# Meshtastic-DIY_v2.net
KiCad netlist of a schematic drawn in EAGLE
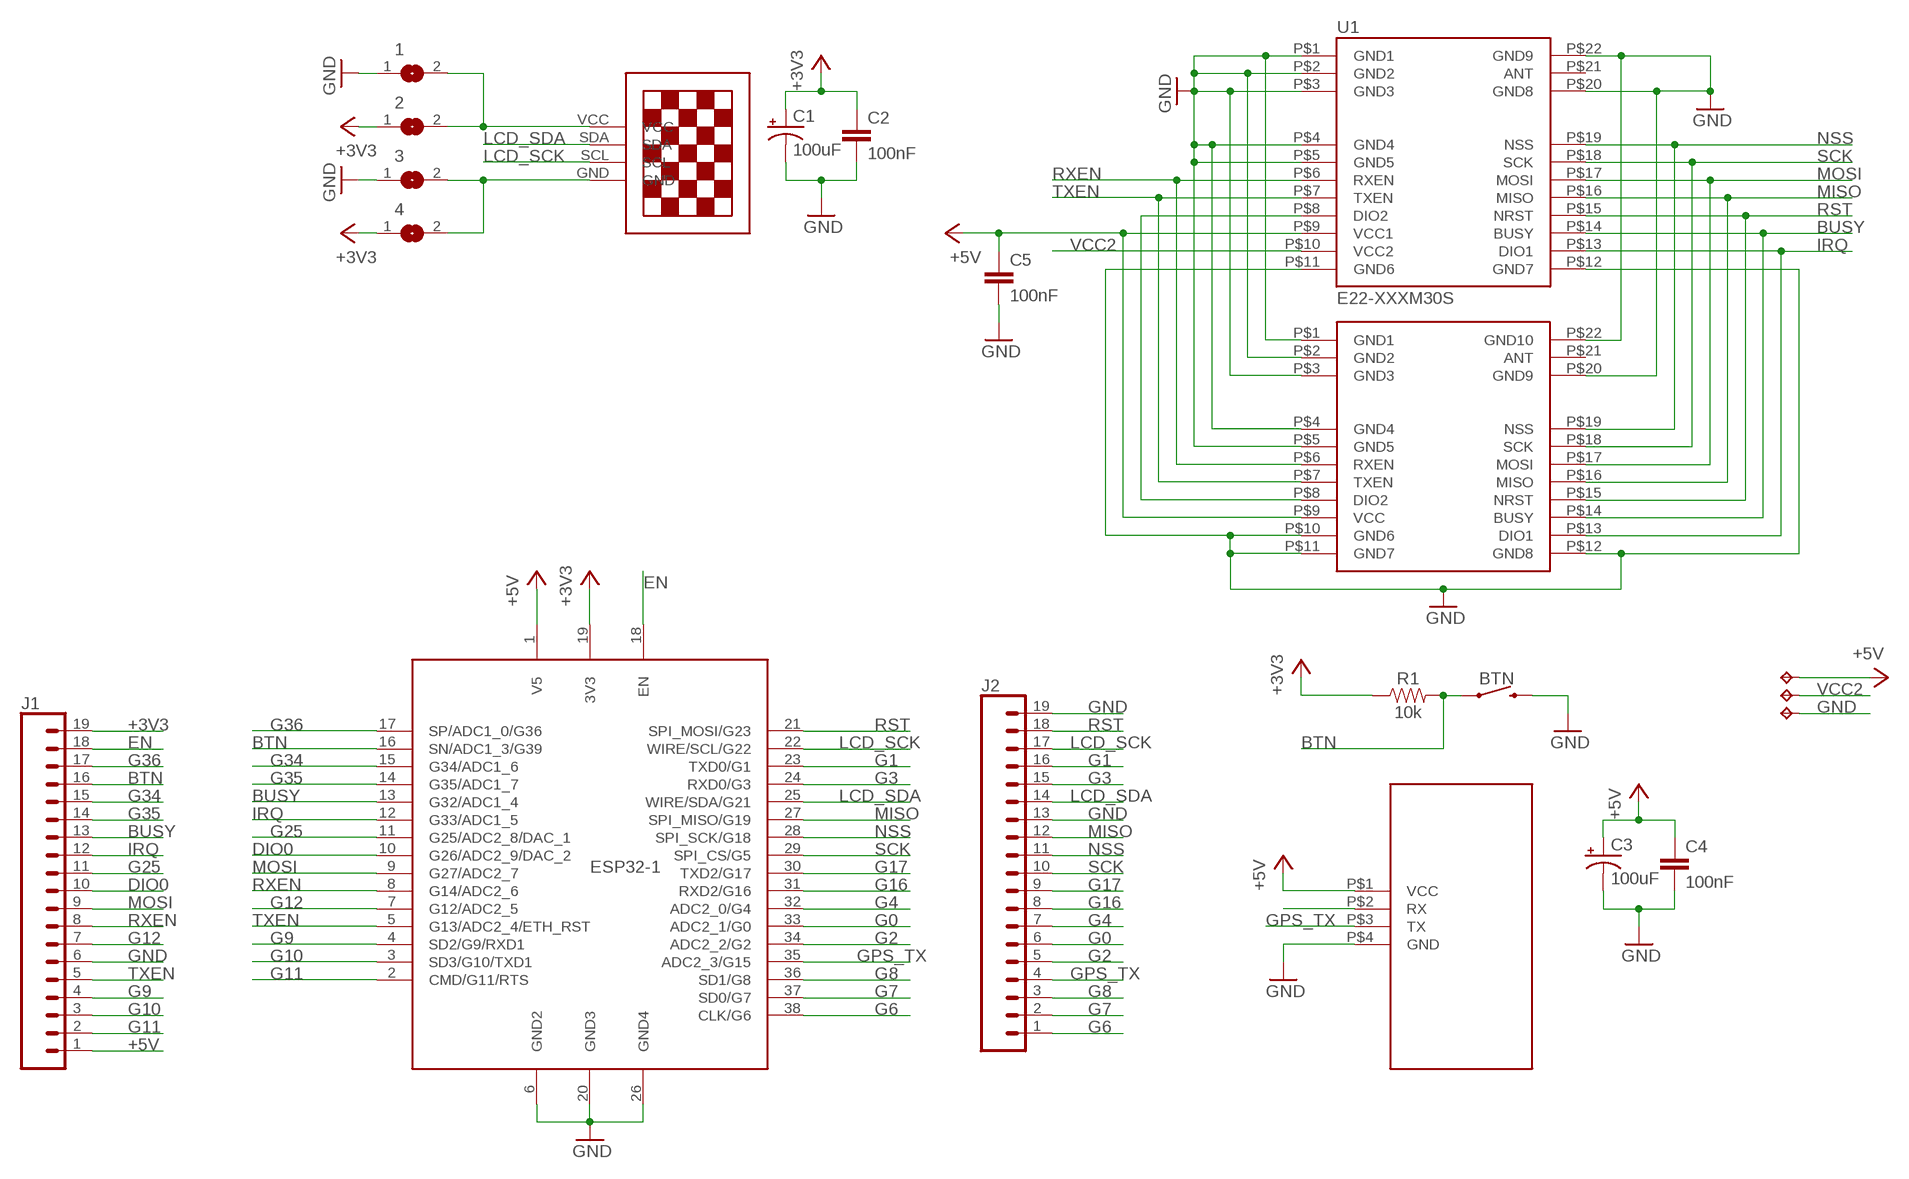
[diagram p0: schematic, sheet 1]

(export (version "E")
  (design (tool "Eeschema 10.0.6"))
  (components
    (comp (ref "1") (value "SJ") (footprint "eagle-import:SJ") (libsource (lib "eagle-import") (part "SJ")))
    (comp (ref "2") (value "SJ") (footprint "eagle-import:SJ") (libsource (lib "eagle-import") (part "SJ")))
    (comp (ref "3") (value "SJ") (footprint "eagle-import:SJ") (libsource (lib "eagle-import") (part "SJ")))
    (comp (ref "4") (value "SJ") (footprint "eagle-import:SJ") (libsource (lib "eagle-import") (part "SJ")))
    (comp (ref "BTN")
      (value "MOMENTARY-SWITCH-SPST-PTH-6.0MM")
      (footprint "eagle-import:TACTILE_SWITCH_PTH_6.0MM")
      (libsource (lib "eagle-import") (part "MOMENTARY-SWITCH-SPST-PTH-6.0MM"))
    )
    (comp (ref "C1")
      (value "100uF")
      (footprint "eagle-import:EIA7343")
      (libsource (lib "eagle-import") (part "100UF-POLAR-EIA7343-10V-10%(TANT)"))
    )
    (comp (ref "C2")
      (value "100nF")
      (footprint "eagle-import:0805")
      (libsource (lib "eagle-import") (part "0.33UF/330NF-0805-50V-10%"))
    )
    (comp (ref "C3")
      (value "100uF")
      (footprint "eagle-import:EIA7343")
      (libsource (lib "eagle-import") (part "100UF-POLAR-EIA7343-10V-10%(TANT)"))
    )
    (comp (ref "C4")
      (value "100nF")
      (footprint "eagle-import:0805")
      (libsource (lib "eagle-import") (part "0.33UF/330NF-0805-50V-10%"))
    )
    (comp (ref "C5")
      (value "100nF")
      (footprint "eagle-import:0805")
      (libsource (lib "eagle-import") (part "0.33UF/330NF-0805-50V-10%"))
    )
    (comp (ref "ESP32-1")
      (value "NODEMCU_ESP32_WROOM_32")
      (footprint "eagle-import:NODEMCU_ESP32_WROOM_32--38PINS")
      (libsource (lib "eagle-import") (part "NODEMCU_ESP32_WROOM_32"))
    )
    (comp (ref "J1")
      (value "CONN_191X19_NO_SILK")
      (footprint "eagle-import:1X19_NO_SILK")
      (libsource (lib "eagle-import") (part "CONN_191X19_NO_SILK"))
    )
    (comp (ref "J2")
      (value "CONN_191X19_NO_SILK")
      (footprint "eagle-import:1X19_NO_SILK")
      (libsource (lib "eagle-import") (part "CONN_191X19_NO_SILK"))
    )
    (comp (ref "R1")
      (value "10k")
      (footprint "eagle-import:1210")
      (libsource (lib "eagle-import") (part "0.1OHM-1210-1/2W-1%"))
    )
    (comp (ref "TP1")
      (value "TPTP14SQ")
      (footprint "eagle-import:TP14SQ")
      (libsource (lib "eagle-import") (part "TPTP14SQ"))
    )
    (comp (ref "TP2")
      (value "TPTP14SQ")
      (footprint "eagle-import:TP14SQ")
      (libsource (lib "eagle-import") (part "TPTP14SQ"))
    )
    (comp (ref "TP3")
      (value "TPTP14SQ")
      (footprint "eagle-import:TP14SQ")
      (libsource (lib "eagle-import") (part "TPTP14SQ"))
    )
    (comp (ref "U$1")
      (value "13\"OLED13\"OLED")
      (footprint "eagle-import:1.3_OLED")
      (libsource (lib "eagle-import") (part "13{dblquote}OLED13{dblquote}OLED"))
    )
    (comp (ref "U$2")
      (value "E22-XXXM22S")
      (footprint "eagle-import:E22-XXXM22S")
      (libsource (lib "eagle-import") (part "E22-XXXM22S"))
    )
    (comp (ref "U$3")
      (value "GPS-NEO")
      (footprint "eagle-import:GPS-NEO")
      (libsource (lib "eagle-import") (part "GPS-NEO"))
    )
    (comp (ref "U1")
      (value "E22-XXXM30S")
      (footprint "eagle-import:E22-XXXM30S")
      (libsource (lib "eagle-import") (part "E22-XXXM30S"))
    )
  )
  (nets
    (net (code "1") (name "+3V3") (class "Default")
      (node (ref "2") (pin "1") (pinfunction "1_1") (pintype "passive"))
      (node (ref "4") (pin "1") (pinfunction "1_1") (pintype "passive"))
      (node (ref "C1") (pin "A") (pinfunction "+_A") (pintype "passive"))
      (node (ref "C2") (pin "1") (pinfunction "1_1") (pintype "passive"))
      (node (ref "ESP32-1") (pin "19") (pinfunction "3V3_19") (pintype "power_in"))
      (node (ref "J1") (pin "19") (pinfunction "19_19") (pintype "passive"))
      (node (ref "R1") (pin "1") (pinfunction "1_1") (pintype "passive"))
    )
    (net (code "2") (name "+5V") (class "Default")
      (node (ref "C3") (pin "A") (pinfunction "+_A") (pintype "passive"))
      (node (ref "C4") (pin "1") (pinfunction "1_1") (pintype "passive"))
      (node (ref "C5") (pin "1") (pinfunction "1_1") (pintype "passive"))
      (node (ref "ESP32-1") (pin "1") (pinfunction "V5_1") (pintype "power_in"))
      (node (ref "J1") (pin "1") (pinfunction "1_1") (pintype "passive"))
      (node (ref "TP1") (pin "TP") (pinfunction "TP_TP") (pintype "input"))
      (node (ref "U$2") (pin "P$9") (pinfunction "VCC_P$9") (pintype "bidirectional"))
      (node (ref "U$3") (pin "P$1") (pinfunction "VCC_P$1") (pintype "bidirectional"))
      (node (ref "U1") (pin "P$9") (pinfunction "VCC1_P$9") (pintype "bidirectional"))
    )
    (net (code "3") (name "/BTN") (class "Default")
      (node (ref "BTN") (pin "1") (pinfunction "1_1") (pintype "passive"))
      (node (ref "ESP32-1") (pin "16") (pinfunction "SN/ADC1_3/G39_16") (pintype "bidirectional"))
      (node (ref "J1") (pin "16") (pinfunction "16_16") (pintype "passive"))
      (node (ref "R1") (pin "2") (pinfunction "2_2") (pintype "passive"))
    )
    (net (code "4") (name "/BUSY") (class "Default")
      (node (ref "ESP32-1") (pin "13") (pinfunction "G32/ADC1_4_13") (pintype "bidirectional"))
      (node (ref "J1") (pin "13") (pinfunction "13_13") (pintype "passive"))
      (node (ref "U$2") (pin "P$14") (pinfunction "BUSY_P$14") (pintype "bidirectional"))
      (node (ref "U1") (pin "P$14") (pinfunction "BUSY_P$14") (pintype "bidirectional"))
    )
    (net (code "5") (name "/DIO0") (class "Default")
      (node (ref "ESP32-1") (pin "10") (pinfunction "G26/ADC2_9/DAC_2_10") (pintype "bidirectional"))
      (node (ref "J1") (pin "10") (pinfunction "10_10") (pintype "passive"))
    )
    (net (code "6") (name "/EN") (class "Default")
      (node (ref "ESP32-1") (pin "18") (pinfunction "EN_18") (pintype "bidirectional"))
      (node (ref "J1") (pin "18") (pinfunction "18_18") (pintype "passive"))
    )
    (net (code "7") (name "/G0") (class "Default")
      (node (ref "ESP32-1") (pin "33") (pinfunction "ADC2_1/G0_33") (pintype "bidirectional"))
      (node (ref "J2") (pin "6") (pinfunction "6_6") (pintype "passive"))
    )
    (net (code "8") (name "/G1") (class "Default")
      (node (ref "ESP32-1") (pin "23") (pinfunction "TXD0/G1_23") (pintype "bidirectional"))
      (node (ref "J2") (pin "16") (pinfunction "16_16") (pintype "passive"))
    )
    (net (code "9") (name "/G2") (class "Default")
      (node (ref "ESP32-1") (pin "34") (pinfunction "ADC2_2/G2_34") (pintype "bidirectional"))
      (node (ref "J2") (pin "5") (pinfunction "5_5") (pintype "passive"))
    )
    (net (code "10") (name "/G3") (class "Default")
      (node (ref "ESP32-1") (pin "24") (pinfunction "RXD0/G3_24") (pintype "bidirectional"))
      (node (ref "J2") (pin "15") (pinfunction "15_15") (pintype "passive"))
    )
    (net (code "11") (name "/G4") (class "Default")
      (node (ref "ESP32-1") (pin "32") (pinfunction "ADC2_0/G4_32") (pintype "bidirectional"))
      (node (ref "J2") (pin "7") (pinfunction "7_7") (pintype "passive"))
    )
    (net (code "12") (name "/G6") (class "Default")
      (node (ref "ESP32-1") (pin "38") (pinfunction "CLK/G6_38") (pintype "bidirectional"))
      (node (ref "J2") (pin "1") (pinfunction "1_1") (pintype "passive"))
    )
    (net (code "13") (name "/G7") (class "Default")
      (node (ref "ESP32-1") (pin "37") (pinfunction "SD0/G7_37") (pintype "bidirectional"))
      (node (ref "J2") (pin "2") (pinfunction "2_2") (pintype "passive"))
    )
    (net (code "14") (name "/G8") (class "Default")
      (node (ref "ESP32-1") (pin "36") (pinfunction "SD1/G8_36") (pintype "bidirectional"))
      (node (ref "J2") (pin "3") (pinfunction "3_3") (pintype "passive"))
    )
    (net (code "15") (name "/G9") (class "Default")
      (node (ref "ESP32-1") (pin "4") (pinfunction "SD2/G9/RXD1_4") (pintype "bidirectional"))
      (node (ref "J1") (pin "4") (pinfunction "4_4") (pintype "passive"))
    )
    (net (code "16") (name "/G10") (class "Default")
      (node (ref "ESP32-1") (pin "3") (pinfunction "SD3/G10/TXD1_3") (pintype "bidirectional"))
      (node (ref "J1") (pin "3") (pinfunction "3_3") (pintype "passive"))
    )
    (net (code "17") (name "/G11") (class "Default")
      (node (ref "ESP32-1") (pin "2") (pinfunction "CMD/G11/RTS_2") (pintype "power_in"))
      (node (ref "J1") (pin "2") (pinfunction "2_2") (pintype "passive"))
    )
    (net (code "18") (name "/G12") (class "Default")
      (node (ref "ESP32-1") (pin "7") (pinfunction "G12/ADC2_5_7") (pintype "bidirectional"))
      (node (ref "J1") (pin "7") (pinfunction "7_7") (pintype "passive"))
    )
    (net (code "19") (name "/G16") (class "Default")
      (node (ref "ESP32-1") (pin "31") (pinfunction "RXD2/G16_31") (pintype "bidirectional"))
      (node (ref "J2") (pin "8") (pinfunction "8_8") (pintype "passive"))
    )
    (net (code "20") (name "/G17") (class "Default")
      (node (ref "ESP32-1") (pin "30") (pinfunction "TXD2/G17_30") (pintype "bidirectional"))
      (node (ref "J2") (pin "9") (pinfunction "9_9") (pintype "passive"))
    )
    (net (code "21") (name "/G25") (class "Default")
      (node (ref "ESP32-1") (pin "11") (pinfunction "G25/ADC2_8/DAC_1_11") (pintype "bidirectional"))
      (node (ref "J1") (pin "11") (pinfunction "11_11") (pintype "passive"))
    )
    (net (code "22") (name "/G34") (class "Default")
      (node (ref "ESP32-1") (pin "15") (pinfunction "G34/ADC1_6_15") (pintype "bidirectional"))
      (node (ref "J1") (pin "15") (pinfunction "15_15") (pintype "passive"))
    )
    (net (code "23") (name "/G35") (class "Default")
      (node (ref "ESP32-1") (pin "14") (pinfunction "G35/ADC1_7_14") (pintype "bidirectional"))
      (node (ref "J1") (pin "14") (pinfunction "14_14") (pintype "passive"))
    )
    (net (code "24") (name "/G36") (class "Default")
      (node (ref "ESP32-1") (pin "17") (pinfunction "SP/ADC1_0/G36_17") (pintype "bidirectional"))
      (node (ref "J1") (pin "17") (pinfunction "17_17") (pintype "passive"))
    )
    (net (code "25") (name "/GPS_TX") (class "Default")
      (node (ref "ESP32-1") (pin "35") (pinfunction "ADC2_3/G15_35") (pintype "bidirectional"))
      (node (ref "J2") (pin "4") (pinfunction "4_4") (pintype "passive"))
      (node (ref "U$3") (pin "P$3") (pinfunction "TX_P$3") (pintype "bidirectional"))
    )
    (net (code "26") (name "/IRQ") (class "Default")
      (node (ref "ESP32-1") (pin "12") (pinfunction "G33/ADC1_5_12") (pintype "bidirectional"))
      (node (ref "J1") (pin "12") (pinfunction "12_12") (pintype "passive"))
      (node (ref "U$2") (pin "P$13") (pinfunction "DIO1_P$13") (pintype "bidirectional"))
      (node (ref "U1") (pin "P$13") (pinfunction "DIO1_P$13") (pintype "bidirectional"))
    )
    (net (code "27") (name "/LCD_SCK") (class "Default")
      (node (ref "ESP32-1") (pin "22") (pinfunction "WIRE/SCL/G22_22") (pintype "bidirectional"))
      (node (ref "J2") (pin "17") (pinfunction "17_17") (pintype "passive"))
      (node (ref "U$1") (pin "SCL") (pinfunction "SCL_SCL") (pintype "bidirectional"))
    )
    (net (code "28") (name "/LCD_SDA") (class "Default")
      (node (ref "ESP32-1") (pin "25") (pinfunction "WIRE/SDA/G21_25") (pintype "bidirectional"))
      (node (ref "J2") (pin "14") (pinfunction "14_14") (pintype "passive"))
      (node (ref "U$1") (pin "SDA") (pinfunction "SDA_SDA") (pintype "bidirectional"))
    )
    (net (code "29") (name "/MISO") (class "Default")
      (node (ref "ESP32-1") (pin "27") (pinfunction "SPI_MISO/G19_27") (pintype "bidirectional"))
      (node (ref "J2") (pin "12") (pinfunction "12_12") (pintype "passive"))
      (node (ref "U$2") (pin "P$16") (pinfunction "MISO_P$16") (pintype "bidirectional"))
      (node (ref "U1") (pin "P$16") (pinfunction "MISO_P$16") (pintype "bidirectional"))
    )
    (net (code "30") (name "/MOSI") (class "Default")
      (node (ref "ESP32-1") (pin "9") (pinfunction "G27/ADC2_7_9") (pintype "bidirectional"))
      (node (ref "J1") (pin "9") (pinfunction "9_9") (pintype "passive"))
      (node (ref "U$2") (pin "P$17") (pinfunction "MOSI_P$17") (pintype "bidirectional"))
      (node (ref "U1") (pin "P$17") (pinfunction "MOSI_P$17") (pintype "bidirectional"))
    )
    (net (code "31") (name "/NSS") (class "Default")
      (node (ref "ESP32-1") (pin "28") (pinfunction "SPI_SCK/G18_28") (pintype "bidirectional"))
      (node (ref "J2") (pin "11") (pinfunction "11_11") (pintype "passive"))
      (node (ref "U$2") (pin "P$19") (pinfunction "NSS_P$19") (pintype "bidirectional"))
      (node (ref "U1") (pin "P$19") (pinfunction "NSS_P$19") (pintype "bidirectional"))
    )
    (net (code "32") (name "/RST") (class "Default")
      (node (ref "ESP32-1") (pin "21") (pinfunction "SPI_MOSI/G23_21") (pintype "bidirectional"))
      (node (ref "J2") (pin "18") (pinfunction "18_18") (pintype "passive"))
      (node (ref "U$2") (pin "P$15") (pinfunction "NRST_P$15") (pintype "bidirectional"))
      (node (ref "U1") (pin "P$15") (pinfunction "NRST_P$15") (pintype "bidirectional"))
    )
    (net (code "33") (name "/RXEN") (class "Default")
      (node (ref "ESP32-1") (pin "8") (pinfunction "G14/ADC2_6_8") (pintype "bidirectional"))
      (node (ref "J1") (pin "8") (pinfunction "8_8") (pintype "passive"))
      (node (ref "U$2") (pin "P$6") (pinfunction "RXEN_P$6") (pintype "bidirectional"))
      (node (ref "U1") (pin "P$6") (pinfunction "RXEN_P$6") (pintype "bidirectional"))
    )
    (net (code "34") (name "/SCK") (class "Default")
      (node (ref "ESP32-1") (pin "29") (pinfunction "SPI_CS/G5_29") (pintype "bidirectional"))
      (node (ref "J2") (pin "10") (pinfunction "10_10") (pintype "passive"))
      (node (ref "U$2") (pin "P$18") (pinfunction "SCK_P$18") (pintype "bidirectional"))
      (node (ref "U1") (pin "P$18") (pinfunction "SCK_P$18") (pintype "bidirectional"))
    )
    (net (code "35") (name "/TXEN") (class "Default")
      (node (ref "ESP32-1") (pin "5") (pinfunction "G13/ADC2_4/ETH_RST_5") (pintype "bidirectional"))
      (node (ref "J1") (pin "5") (pinfunction "5_5") (pintype "passive"))
      (node (ref "U$2") (pin "P$7") (pinfunction "TXEN_P$7") (pintype "bidirectional"))
      (node (ref "U1") (pin "P$7") (pinfunction "TXEN_P$7") (pintype "bidirectional"))
    )
    (net (code "36") (name "/VCC2") (class "Default")
      (node (ref "TP2") (pin "TP") (pinfunction "TP_TP") (pintype "input"))
      (node (ref "U1") (pin "P$10") (pinfunction "VCC2_P$10") (pintype "bidirectional"))
    )
    (net (code "37") (name "GND") (class "Default")
      (node (ref "1") (pin "1") (pinfunction "1_1") (pintype "passive"))
      (node (ref "3") (pin "1") (pinfunction "1_1") (pintype "passive"))
      (node (ref "BTN") (pin "3") (pinfunction "2_3") (pintype "passive"))
      (node (ref "C1") (pin "C") (pinfunction "-_C") (pintype "passive"))
      (node (ref "C2") (pin "2") (pinfunction "2_2") (pintype "passive"))
      (node (ref "C3") (pin "C") (pinfunction "-_C") (pintype "passive"))
      (node (ref "C4") (pin "2") (pinfunction "2_2") (pintype "passive"))
      (node (ref "C5") (pin "2") (pinfunction "2_2") (pintype "passive"))
      (node (ref "ESP32-1") (pin "20") (pinfunction "GND3_20") (pintype "power_in"))
      (node (ref "ESP32-1") (pin "26") (pinfunction "GND4_26") (pintype "power_in"))
      (node (ref "ESP32-1") (pin "6") (pinfunction "GND2_6") (pintype "power_in"))
      (node (ref "J1") (pin "6") (pinfunction "6_6") (pintype "passive"))
      (node (ref "J2") (pin "13") (pinfunction "13_13") (pintype "passive"))
      (node (ref "J2") (pin "19") (pinfunction "19_19") (pintype "passive"))
      (node (ref "TP3") (pin "TP") (pinfunction "TP_TP") (pintype "input"))
      (node (ref "U$2") (pin "P$1") (pinfunction "GND1_P$1") (pintype "bidirectional"))
      (node (ref "U$2") (pin "P$10") (pinfunction "GND6_P$10") (pintype "bidirectional"))
      (node (ref "U$2") (pin "P$11") (pinfunction "GND7_P$11") (pintype "bidirectional"))
      (node (ref "U$2") (pin "P$12") (pinfunction "GND8_P$12") (pintype "bidirectional"))
      (node (ref "U$2") (pin "P$2") (pinfunction "GND2_P$2") (pintype "bidirectional"))
      (node (ref "U$2") (pin "P$20") (pinfunction "GND9_P$20") (pintype "bidirectional"))
      (node (ref "U$2") (pin "P$22") (pinfunction "GND10_P$22") (pintype "bidirectional"))
      (node (ref "U$2") (pin "P$3") (pinfunction "GND3_P$3") (pintype "bidirectional"))
      (node (ref "U$2") (pin "P$4") (pinfunction "GND4_P$4") (pintype "bidirectional"))
      (node (ref "U$2") (pin "P$5") (pinfunction "GND5_P$5") (pintype "bidirectional"))
      (node (ref "U$3") (pin "P$4") (pinfunction "GND_P$4") (pintype "bidirectional"))
      (node (ref "U1") (pin "P$1") (pinfunction "GND1_P$1") (pintype "bidirectional"))
      (node (ref "U1") (pin "P$11") (pinfunction "GND6_P$11") (pintype "bidirectional"))
      (node (ref "U1") (pin "P$12") (pinfunction "GND7_P$12") (pintype "bidirectional"))
      (node (ref "U1") (pin "P$2") (pinfunction "GND2_P$2") (pintype "bidirectional"))
      (node (ref "U1") (pin "P$20") (pinfunction "GND8_P$20") (pintype "bidirectional"))
      (node (ref "U1") (pin "P$22") (pinfunction "GND9_P$22") (pintype "bidirectional"))
      (node (ref "U1") (pin "P$3") (pinfunction "GND3_P$3") (pintype "bidirectional"))
      (node (ref "U1") (pin "P$4") (pinfunction "GND4_P$4") (pintype "bidirectional"))
      (node (ref "U1") (pin "P$5") (pinfunction "GND5_P$5") (pintype "bidirectional"))
    )
    (net (code "38") (name "Net-(1-Pad2)") (class "Default")
      (node (ref "1") (pin "2") (pinfunction "2_2") (pintype "passive"))
      (node (ref "2") (pin "2") (pinfunction "2_2") (pintype "passive"))
      (node (ref "U$1") (pin "VCC") (pinfunction "VCC_VCC") (pintype "bidirectional"))
    )
    (net (code "39") (name "Net-(3-Pad2)") (class "Default")
      (node (ref "3") (pin "2") (pinfunction "2_2") (pintype "passive"))
      (node (ref "4") (pin "2") (pinfunction "2_2") (pintype "passive"))
      (node (ref "U$1") (pin "GND") (pinfunction "GND_GND") (pintype "bidirectional"))
    )
    (net (code "40") (name "Net-(U$2-DIO2)") (class "Default")
      (node (ref "U$2") (pin "P$8") (pinfunction "DIO2_P$8") (pintype "bidirectional"))
      (node (ref "U1") (pin "P$8") (pinfunction "DIO2_P$8") (pintype "bidirectional"))
    )
    (net (code "41") (name "unconnected-(U$2-ANT-PadP$21)") (class "Default")
      (node (ref "U$2") (pin "P$21") (pinfunction "ANT_P$21") (pintype "bidirectional"))
    )
    (net (code "42") (name "unconnected-(U$3-RX-PadP$2)") (class "Default")
      (node (ref "U$3") (pin "P$2") (pinfunction "RX_P$2") (pintype "bidirectional"))
    )
    (net (code "43") (name "unconnected-(U1-ANT-PadP$21)") (class "Default")
      (node (ref "U1") (pin "P$21") (pinfunction "ANT_P$21") (pintype "bidirectional"))
    )
  )
)
